# Tracer-1_3.net
KiCad netlist of a schematic drawn in EasyEDA Pro
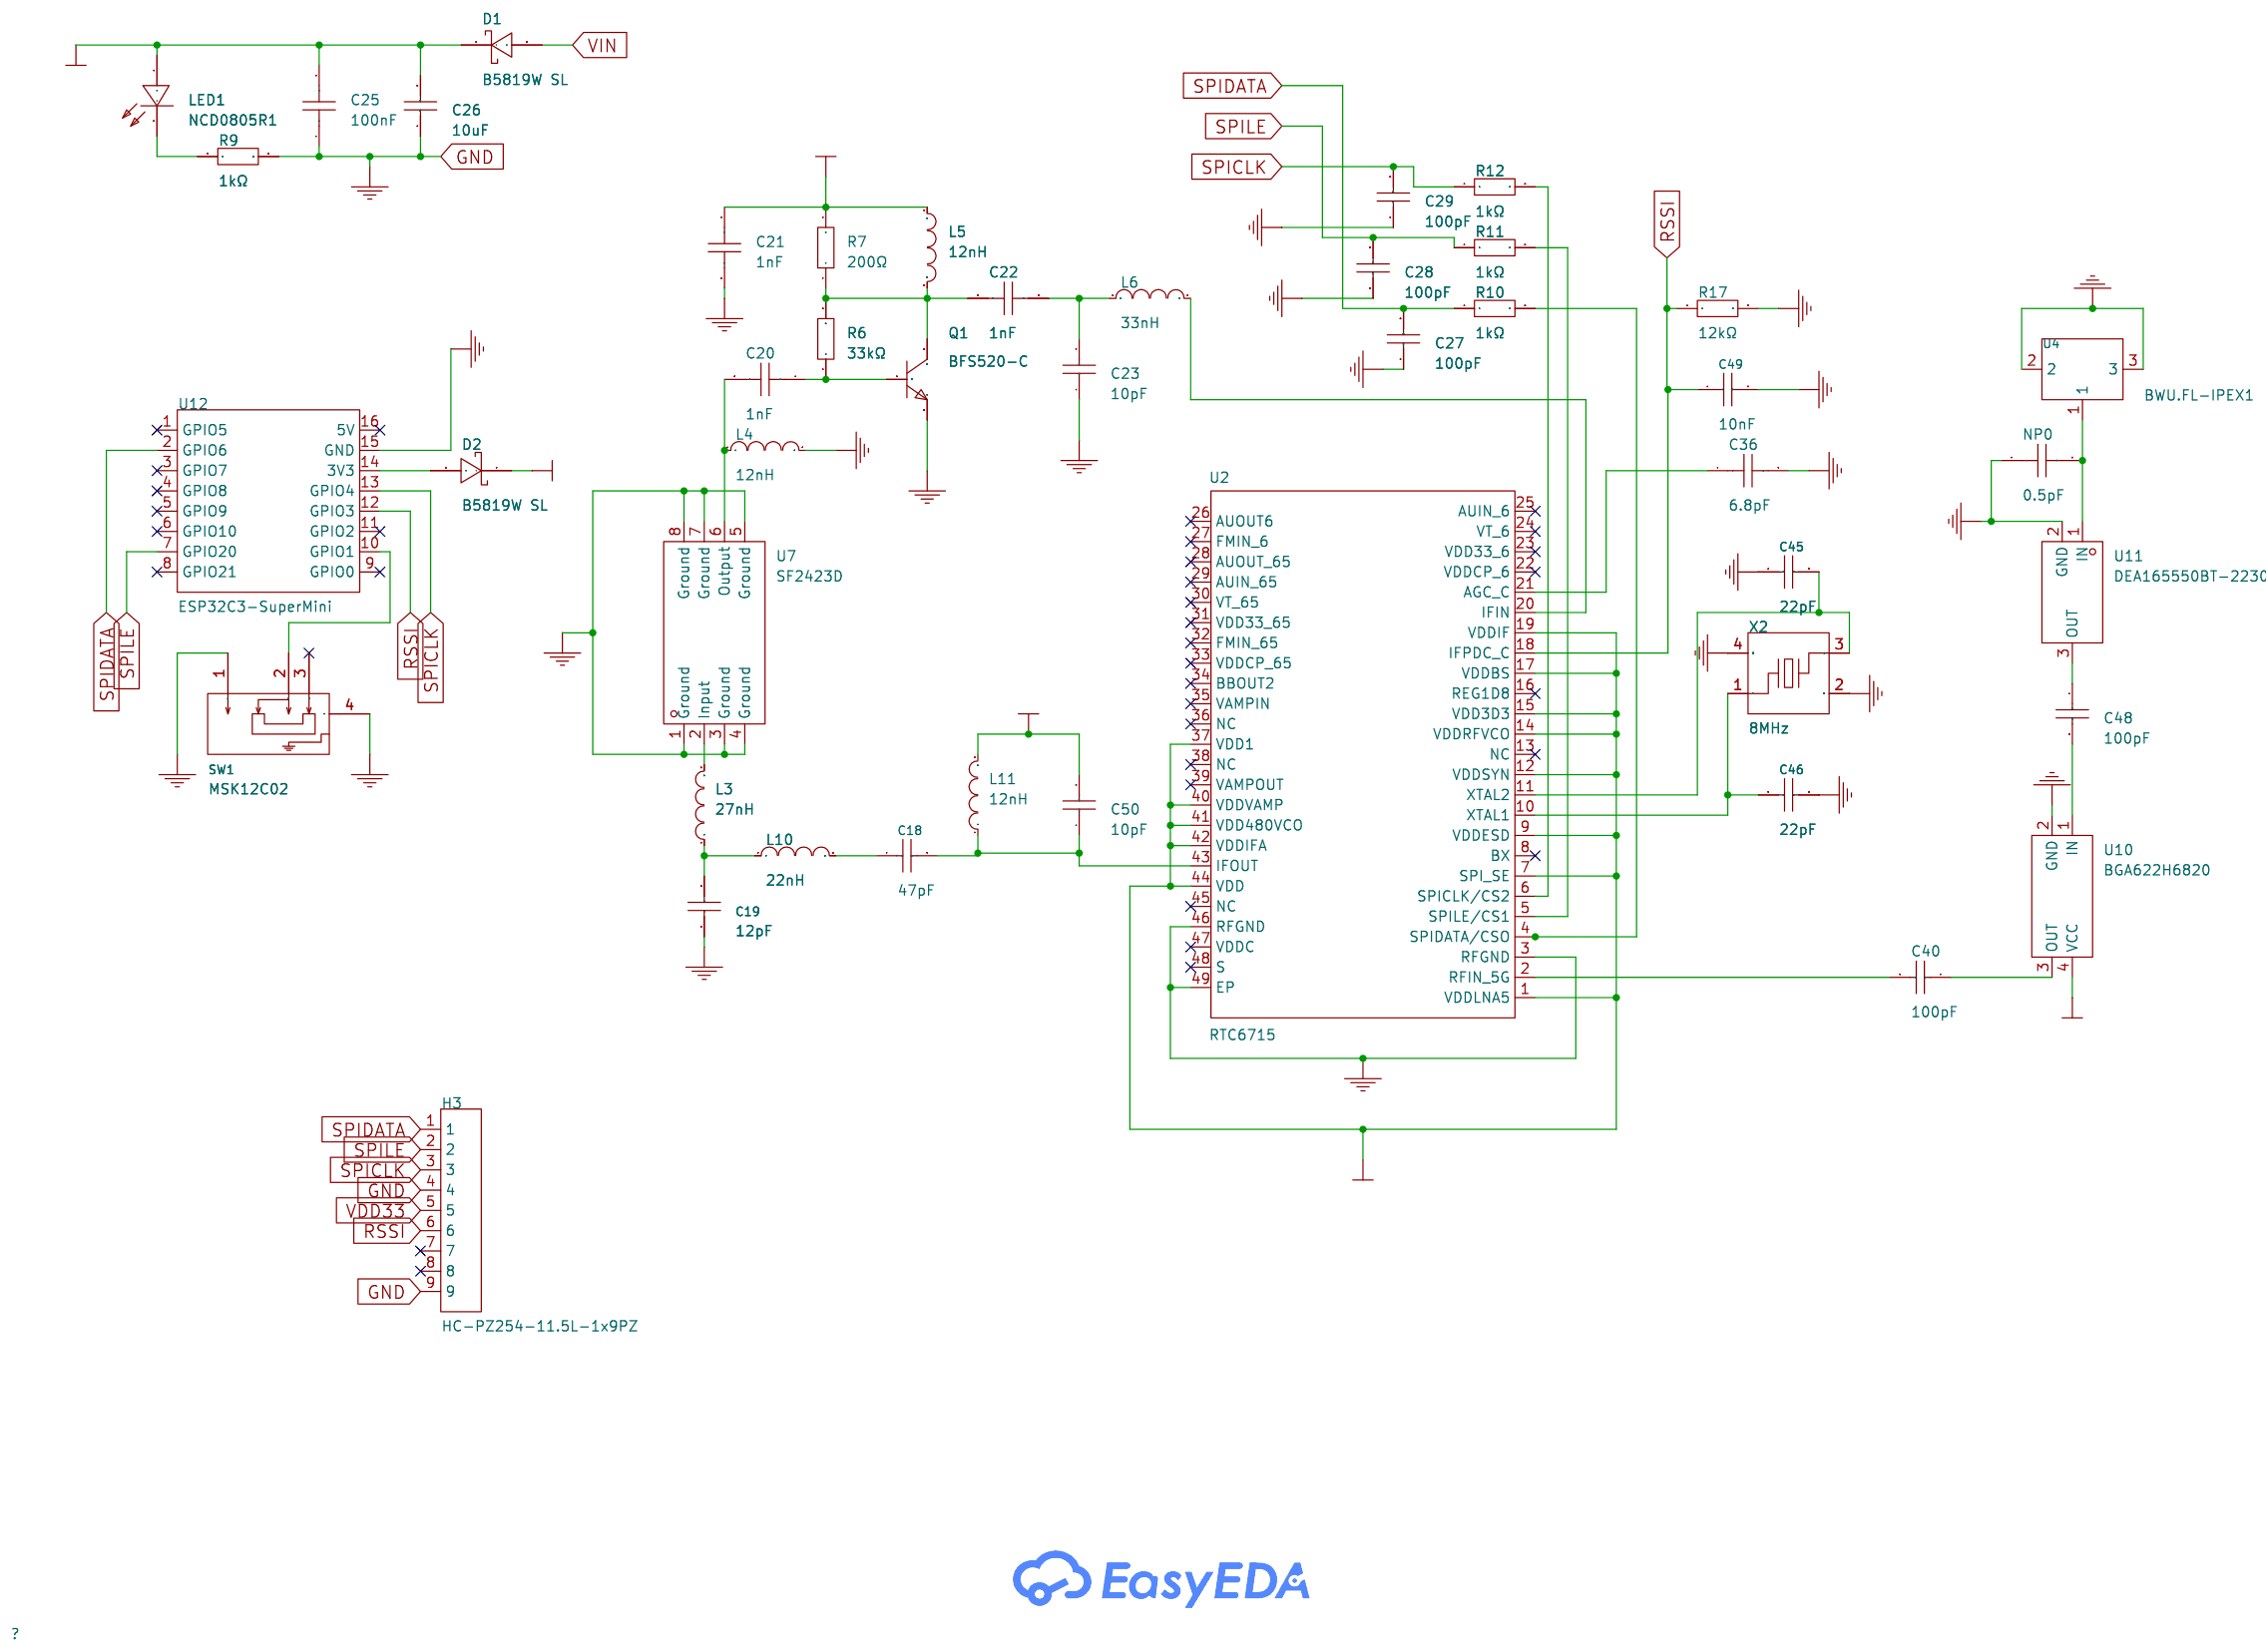
[diagram p0: schematic sheet]

(export (version "E")
  (design (tool "Eeschema 10.0.6"))
  (components
    (comp (ref "C18")
      (value "47pF")
      (footprint "easyedapro:C0402")
      (fields
        (field (name "Manufacturer Part") "CC0402JRNPO9BN470")
        (field (name "Manufacturer") "YAGEO(国巨)")
      )
      (libsource (lib "easyedapro") (part "CC0402JRNPO9BN470"))
    )
    (comp (ref "C19")
      (value "12pF")
      (footprint "easyedapro:C0402")
      (fields
        (field (name "Manufacturer Part") "GRM1555C1H120JA01D")
        (field (name "Manufacturer") "muRata(村田)")
      )
      (libsource (lib "easyedapro") (part "GRM1555C1H120JA01D"))
    )
    (comp (ref "C20")
      (value "1nF")
      (footprint "easyedapro:C0402")
      (fields
        (field (name "Manufacturer Part") "GRM155R71H102KA01D")
        (field (name "Manufacturer") "muRata(村田)")
      )
      (libsource (lib "easyedapro") (part "GRM155R71H102KA01D"))
    )
    (comp (ref "C21")
      (value "1nF")
      (footprint "easyedapro:C0402")
      (fields
        (field (name "Manufacturer Part") "GRM155R71H102KA01D")
        (field (name "Manufacturer") "muRata(村田)")
      )
      (libsource (lib "easyedapro") (part "GRM155R71H102KA01D"))
    )
    (comp (ref "C22")
      (value "1nF")
      (footprint "easyedapro:C0402")
      (fields
        (field (name "Manufacturer Part") "GRM155R71H102KA01D")
        (field (name "Manufacturer") "muRata(村田)")
      )
      (libsource (lib "easyedapro") (part "GRM155R71H102KA01D"))
    )
    (comp (ref "C23")
      (value "10pF")
      (footprint "easyedapro:C0402")
      (fields
        (field (name "Manufacturer Part") "GRM1555C1H100JA01D")
        (field (name "Manufacturer") "muRata(村田)")
      )
      (libsource (lib "easyedapro") (part "GRM1555C1H100JA01D"))
    )
    (comp (ref "C25")
      (value "100nF")
      (footprint "easyedapro:C0402")
      (fields
        (field (name "Manufacturer Part") "CL05B104KO5NNNC")
        (field (name "Manufacturer") "SAMSUNG(三星)")
      )
      (libsource (lib "easyedapro") (part "CL05B104KO5NNNC"))
    )
    (comp (ref "C26")
      (value "10uF")
      (fields
        (field (name "Manufacturer Part") "GRM155R60J106ME44D")
        (field (name "Manufacturer") "muRata(村田)")
      )
      (libsource (lib "easyedapro") (part "CL05A106MQ5NUNC"))
    )
    (comp (ref "C27")
      (value "100pF")
      (footprint "easyedapro:C0402")
      (fields
        (field (name "Manufacturer Part") "GRM1555C1H101JA01D")
        (field (name "Manufacturer") "muRata(村田)")
      )
      (libsource (lib "easyedapro") (part "GRM1555C1H101JA01D"))
    )
    (comp (ref "C28")
      (value "100pF")
      (footprint "easyedapro:C0402")
      (fields
        (field (name "Manufacturer Part") "GRM1555C1H101JA01D")
        (field (name "Manufacturer") "muRata(村田)")
      )
      (libsource (lib "easyedapro") (part "GRM1555C1H101JA01D"))
    )
    (comp (ref "C29")
      (value "100pF")
      (footprint "easyedapro:C0402")
      (fields
        (field (name "Manufacturer Part") "GRM1555C1H101JA01D")
        (field (name "Manufacturer") "muRata(村田)")
      )
      (libsource (lib "easyedapro") (part "GRM1555C1H101JA01D"))
    )
    (comp (ref "C36")
      (value "6.8pF")
      (footprint "easyedapro:C0402")
      (fields
        (field (name "Manufacturer Part") "CC0402CRNPO9BN6R8")
        (field (name "Manufacturer") "YAGEO(国巨)")
      )
      (libsource (lib "easyedapro") (part "CC0402CRNPO9BN6R8"))
    )
    (comp (ref "C40")
      (value "100pF")
      (footprint "easyedapro:C0402")
      (fields
        (field (name "Manufacturer Part") "GRM1555C1H101JA01D")
        (field (name "Manufacturer") "muRata(村田)")
      )
      (libsource (lib "easyedapro") (part "GRM1555C1H101JA01D"))
    )
    (comp (ref "C45")
      (value "22pF")
      (footprint "easyedapro:C0402")
      (fields
        (field (name "Manufacturer Part") "CC0402JRNPO9BN220")
        (field (name "Manufacturer") "YAGEO(国巨)")
      )
      (libsource (lib "easyedapro") (part "CC0402JRNPO9BN220"))
    )
    (comp (ref "C46")
      (value "22pF")
      (footprint "easyedapro:C0402")
      (fields
        (field (name "Manufacturer Part") "CC0402JRNPO9BN220")
        (field (name "Manufacturer") "YAGEO(国巨)")
      )
      (libsource (lib "easyedapro") (part "CC0402JRNPO9BN220"))
    )
    (comp (ref "C48")
      (value "100pF")
      (footprint "easyedapro:C0402")
      (fields
        (field (name "Manufacturer Part") "GRM1555C1H101JA01D")
        (field (name "Manufacturer") "muRata(村田)")
      )
      (libsource (lib "easyedapro") (part "GRM1555C1H101JA01D"))
    )
    (comp (ref "C49")
      (value "10nF")
      (footprint "easyedapro:C0402")
      (description "Capacitance:10nF Tolerance:±10% Tolerance:±10% Voltage Rating:50V Temperature Coefficient:X7R")
      (fields
        (field (name "Manufacturer Part") "CC0402KRX7R9BB103")
        (field (name "Manufacturer") "YAGEO(国巨)")
      )
      (libsource (lib "easyedapro") (part "CC0402KRX7R9BB103"))
    )
    (comp (ref "C50")
      (value "10pF")
      (footprint "easyedapro:C0402")
      (fields
        (field (name "Manufacturer Part") "GRM1555C1H100JA01D")
        (field (name "Manufacturer") "muRata(村田)")
      )
      (libsource (lib "easyedapro") (part "GRM1555C1H100JA01D"))
    )
    (comp (ref "D1")
      (value "B5819W SL")
      (footprint "easyedapro:SOD-123_L2.7-W1.6-LS3.7-RD-1")
      (description "Forward Voltage (Vf@If):600mV@1A Reverse Voltage (Vr):40V Rectified Current:1A")
      (fields (field (name "Manufacturer") "CJ(江苏长电/长晶)"))
      (libsource (lib "easyedapro") (part "B5819W_C8598"))
    )
    (comp (ref "D2")
      (value "B5819W SL")
      (footprint "easyedapro:SOD-123_L2.7-W1.6-LS3.7-RD-1")
      (description "Forward Voltage (Vf@If):600mV@1A Reverse Voltage (Vr):40V Rectified Current:1A")
      (fields (field (name "Manufacturer") "CJ(江苏长电/长晶)"))
      (libsource (lib "easyedapro") (part "B5819W_C8598"))
    )
    (comp (ref "H3")
      (value "HC-PZ254-11.5L-1x9PZ")
      (footprint "easyedapro:HDR-TH_9P-P2.54-V-M")
      (fields (field (name "Manufacturer") "HC(虹成电子)"))
      (libsource (lib "easyedapro") (part "HC-PZ254-11.5L-1X9PZ"))
    )
    (comp (ref "L3")
      (value "27nH")
      (footprint "easyedapro:L0402-RD")
      (fields (field (name "Manufacturer Part") "LQG15HS27NJ02D") (field (name "Manufacturer") "muRata(村田)"))
      (libsource (lib "easyedapro") (part "LQG15HS27NJ02D"))
    )
    (comp (ref "L4")
      (value "12nH")
      (footprint "easyedapro:L0402")
      (fields (field (name "Manufacturer Part") "LQW15AN12NG00D") (field (name "Manufacturer") "muRata(村田)"))
      (libsource (lib "easyedapro") (part "LQW15AN12NG00D"))
    )
    (comp (ref "L5")
      (value "12nH")
      (footprint "easyedapro:L0402")
      (fields (field (name "Manufacturer Part") "LQW15AN12NG00D") (field (name "Manufacturer") "muRata(村田)"))
      (libsource (lib "easyedapro") (part "LQW15AN12NG00D"))
    )
    (comp (ref "L6")
      (value "33nH")
      (footprint "easyedapro:L0402")
      (fields (field (name "Manufacturer Part") "LQG15HS33NJ02D") (field (name "Manufacturer") "muRata(村田)"))
      (libsource (lib "easyedapro") (part "LQG15HS33NJ02D"))
    )
    (comp (ref "L10")
      (value "22nH")
      (footprint "easyedapro:L0402")
      (fields (field (name "Manufacturer Part") "LQW15AN22NJ00D") (field (name "Manufacturer") "muRata(村田)"))
      (libsource (lib "easyedapro") (part "LQW15AN22NJ00D"))
    )
    (comp (ref "L11")
      (value "12nH")
      (footprint "easyedapro:L0402")
      (fields (field (name "Manufacturer Part") "LQW15AN12NG00D") (field (name "Manufacturer") "muRata(村田)"))
      (libsource (lib "easyedapro") (part "LQW15AN12NG00D"))
    )
    (comp (ref "LED1")
      (value "NCD0805R1")
      (footprint "easyedapro:LED0805-R-RD")
      (fields (field (name "Manufacturer") "国星光电"))
      (libsource (lib "easyedapro") (part "FC-2012HRK-620D"))
    )
    (comp (ref "NP0")
      (value "0.5pF")
      (footprint "easyedapro:C0402")
      (description "Capacitance:0.5pF Voltage Rating:50V Temperature Coefficient:C0G")
      (fields (field (name "Manufacturer Part") "0402CG0R5B500NT") (field (name "Manufacturer") "FH(风华)"))
      (libsource (lib "easyedapro") (part "0402CG0R5B500NT"))
    )
    (comp (ref "Q1")
      (value "BFS520-C")
      (footprint "easyedapro:SOT-323-3_L2.0-W1.3-P1.30-LS2.3-BR")
      (fields (field (name "Manufacturer") "Slkor(萨科微)"))
      (libsource (lib "easyedapro") (part "BFS520-C"))
    )
    (comp (ref "R6")
      (value "33kΩ")
      (footprint "easyedapro:R0402")
      (fields (field (name "Manufacturer Part") "RC0402FR-0733KL") (field (name "Manufacturer") "YAGEO(国巨)"))
      (libsource (lib "easyedapro") (part "RC0402FR-0733KL"))
    )
    (comp (ref "R7")
      (value "200Ω")
      (footprint "easyedapro:R0402")
      (fields (field (name "Manufacturer Part") "RC0402FR-07200RL") (field (name "Manufacturer") "YAGEO(国巨)"))
      (libsource (lib "easyedapro") (part "RC0402FR-07200RL"))
    )
    (comp (ref "R9")
      (value "1kΩ")
      (footprint "easyedapro:R0402")
      (fields (field (name "Manufacturer Part") "RC0402FR-071KL") (field (name "Manufacturer") "YAGEO(国巨)"))
      (libsource (lib "easyedapro") (part "RC0402FR-071KL"))
    )
    (comp (ref "R10")
      (value "1kΩ")
      (footprint "easyedapro:R0402")
      (fields (field (name "Manufacturer Part") "RC0402FR-071KL") (field (name "Manufacturer") "YAGEO(国巨)"))
      (libsource (lib "easyedapro") (part "RC0402FR-071KL"))
    )
    (comp (ref "R11")
      (value "1kΩ")
      (footprint "easyedapro:R0402")
      (fields (field (name "Manufacturer Part") "RC0402FR-071KL") (field (name "Manufacturer") "YAGEO(国巨)"))
      (libsource (lib "easyedapro") (part "RC0402FR-071KL"))
    )
    (comp (ref "R12")
      (value "1kΩ")
      (footprint "easyedapro:R0402")
      (fields (field (name "Manufacturer Part") "RC0402FR-071KL") (field (name "Manufacturer") "YAGEO(国巨)"))
      (libsource (lib "easyedapro") (part "RC0402FR-071KL"))
    )
    (comp (ref "R17")
      (value "12kΩ")
      (footprint "easyedapro:R0402")
      (fields (field (name "Manufacturer Part") "RTT021202FTH") (field (name "Manufacturer") "RALEC(旺诠)"))
      (libsource (lib "easyedapro") (part "RTT021202FTH"))
    )
    (comp (ref "SW1")
      (value "MSK12C02")
      (footprint "easyedapro:SW-TH_MSK12C02")
      (fields (field (name "Manufacturer") "SHOU HAN(首韩)"))
      (libsource (lib "easyedapro") (part "MSK12C02"))
    )
    (comp (ref "U2") (value "RTC6715") (libsource (lib "easyedapro") (part "RTC6715")))
    (comp (ref "U4")
      (value "BWU.FL-IPEX1")
      (footprint "easyedapro:IPEX-SMD_BWIPX-1-001E")
      (fields (field (name "Manufacturer") "BAT WIRELESS(蝙蝠无线)"))
      (libsource (lib "easyedapro") (part "BWU.FL-IPEX1"))
    )
    (comp (ref "U7")
      (value "SF2423D")
      (footprint "easyedapro:FILTER-SMD_8P-L3.8-W3.8-P1.27-BL")
      (fields (field (name "Manufacturer") "muRata(村田)"))
      (libsource (lib "easyedapro") (part "SF2423D"))
    )
    (comp (ref "U10")
      (value "BGA622H6820")
      (footprint "easyedapro:SOT-343-4_L2.0-W1.3-P1.30-LS2.1-BL")
      (fields (field (name "Manufacturer") "Infineon(英飞凌)"))
      (libsource (lib "easyedapro") (part "BGA622H6820"))
    )
    (comp (ref "U11")
      (value "DEA165550BT-2230C2-H")
      (footprint "easyedapro:FILTER-SMD_3P-L1.6-W0.8-L-1")
      (description "Bandwidth:800MHz Filter Type:Bandpass Insertion Loss:0.9dB")
      (fields (field (name "Manufacturer") "TDK"))
      (libsource (lib "easyedapro") (part "DEA165550BT-2230C2-H"))
    )
    (comp (ref "U12")
      (value "ESP32C3-SuperMini")
      (footprint "easyedapro:COMM-SMD_16P-L22.5-W18.0-P2.54-TL")
      (libsource (lib "easyedapro") (part "ESP32C3-SUPERMINI"))
    )
    (comp (ref "X2")
      (value "8MHz")
      (footprint "easyedapro:CRYSTAL-SMD_4P-L3.2-W2.5-BL")
      (fields (field (name "Manufacturer Part") "K3A080001210") (field (name "Manufacturer") "KYX(凯越翔)"))
      (libsource (lib "easyedapro") (part "K3A080001210"))
    )
  )
  (nets
    (net (code "1") (name "GND") (class "Default")
      (node (ref "C19") (pin "1") (pinfunction "1_1") (pintype "input"))
      (node (ref "C21") (pin "2") (pinfunction "2_2") (pintype "unspecified"))
      (node (ref "C23") (pin "1") (pinfunction "1_1") (pintype "input"))
      (node (ref "C25") (pin "1") (pinfunction "1_1") (pintype "unspecified"))
      (node (ref "C26") (pin "1") (pinfunction "1_1") (pintype "input"))
      (node (ref "C27") (pin "1") (pinfunction "1_1") (pintype "input"))
      (node (ref "C28") (pin "1") (pinfunction "1_1") (pintype "input"))
      (node (ref "C29") (pin "1") (pinfunction "1_1") (pintype "input"))
      (node (ref "C36") (pin "2") (pinfunction "2_2") (pintype "unspecified"))
      (node (ref "C45") (pin "1") (pinfunction "1_1") (pintype "input"))
      (node (ref "C46") (pin "2") (pinfunction "2_2") (pintype "input"))
      (node (ref "C49") (pin "2") (pinfunction "2_2") (pintype "input"))
      (node (ref "H3") (pin "4") (pinfunction "4_4") (pintype "unspecified"))
      (node (ref "H3") (pin "9") (pinfunction "9_9") (pintype "unspecified"))
      (node (ref "L4") (pin "2") (pinfunction "2_2") (pintype "unspecified"))
      (node (ref "NP0") (pin "1") (pinfunction "1_1") (pintype "unspecified"))
      (node (ref "Q1") (pin "2") (pinfunction "E_2") (pintype "input"))
      (node (ref "R17") (pin "2") (pinfunction "2_2") (pintype "input"))
      (node (ref "R9") (pin "2") (pinfunction "2_2") (pintype "input"))
      (node (ref "SW1") (pin "1") (pinfunction "1_1") (pintype "input"))
      (node (ref "SW1") (pin "4") (pinfunction "4_4") (pintype "input"))
      (node (ref "U10") (pin "2") (pinfunction "GND_2") (pintype "unspecified"))
      (node (ref "U11") (pin "2") (pinfunction "GND_2") (pintype "unspecified"))
      (node (ref "U12") (pin "15") (pinfunction "GND_15") (pintype "unspecified"))
      (node (ref "U2") (pin "3") (pinfunction "RFGND_3") (pintype "unspecified"))
      (node (ref "U2") (pin "46") (pinfunction "RFGND_46") (pintype "unspecified"))
      (node (ref "U2") (pin "49") (pinfunction "EP_49") (pintype "unspecified"))
      (node (ref "U4") (pin "2") (pinfunction "2_2") (pintype "input"))
      (node (ref "U4") (pin "3") (pinfunction "3_3") (pintype "input"))
      (node (ref "U7") (pin "1") (pinfunction "Ground_1") (pintype "unspecified"))
      (node (ref "U7") (pin "3") (pinfunction "Ground_3") (pintype "unspecified"))
      (node (ref "U7") (pin "4") (pinfunction "Ground_4") (pintype "unspecified"))
      (node (ref "U7") (pin "5") (pinfunction "Ground_5") (pintype "unspecified"))
      (node (ref "U7") (pin "7") (pinfunction "Ground_7") (pintype "unspecified"))
      (node (ref "U7") (pin "8") (pinfunction "Ground_8") (pintype "unspecified"))
      (node (ref "X2") (pin "2") (pinfunction "GND_2") (pintype "input"))
      (node (ref "X2") (pin "4") (pinfunction "GND_4") (pintype "input"))
    )
    (net (code "2") (name "Net-(C18-Pad1)") (class "Default")
      (node (ref "C18") (pin "1") (pinfunction "1_1") (pintype "input"))
      (node (ref "L10") (pin "2") (pinfunction "2_2") (pintype "unspecified"))
    )
    (net (code "3") (name "Net-(C19-Pad2)") (class "Default")
      (node (ref "C19") (pin "2") (pinfunction "2_2") (pintype "input"))
      (node (ref "L10") (pin "1") (pinfunction "1_1") (pintype "unspecified"))
      (node (ref "L3") (pin "1") (pinfunction "1_1") (pintype "unspecified"))
    )
    (net (code "4") (name "Net-(C22-Pad1)") (class "Default")
      (node (ref "C22") (pin "1") (pinfunction "1_1") (pintype "unspecified"))
      (node (ref "C23") (pin "2") (pinfunction "2_2") (pintype "input"))
      (node (ref "L6") (pin "1") (pinfunction "1_1") (pintype "unspecified"))
    )
    (net (code "5") (name "Net-(D2-+)") (class "Default")
      (node (ref "D2") (pin "2") (pinfunction "+_2") (pintype "unspecified"))
      (node (ref "U12") (pin "14") (pinfunction "3V3_14") (pintype "unspecified"))
    )
    (net (code "6") (name "Net-(LED1--)") (class "Default")
      (node (ref "LED1") (pin "2") (pinfunction "-_2") (pintype "unspecified"))
      (node (ref "R9") (pin "1") (pinfunction "1_1") (pintype "input"))
    )
    (net (code "7") (name "Net-(Q1-B)") (class "Default")
      (node (ref "C20") (pin "1") (pinfunction "1_1") (pintype "unspecified"))
      (node (ref "Q1") (pin "1") (pinfunction "B_1") (pintype "input"))
      (node (ref "R6") (pin "1") (pinfunction "1_1") (pintype "input"))
    )
    (net (code "8") (name "Net-(Q1-C)") (class "Default")
      (node (ref "C22") (pin "2") (pinfunction "2_2") (pintype "unspecified"))
      (node (ref "L5") (pin "2") (pinfunction "2_2") (pintype "unspecified"))
      (node (ref "Q1") (pin "3") (pinfunction "C_3") (pintype "input"))
      (node (ref "R6") (pin "2") (pinfunction "2_2") (pintype "input"))
      (node (ref "R7") (pin "1") (pinfunction "1_1") (pintype "input"))
    )
    (net (code "9") (name "Net-(U2-AGC_C)") (class "Default")
      (node (ref "C36") (pin "1") (pinfunction "1_1") (pintype "unspecified"))
      (node (ref "U2") (pin "21") (pinfunction "AGC_C_21") (pintype "unspecified"))
    )
    (net (code "10") (name "Net-(U2-IFIN)") (class "Default")
      (node (ref "L6") (pin "2") (pinfunction "2_2") (pintype "unspecified"))
      (node (ref "U2") (pin "20") (pinfunction "IFIN_20") (pintype "unspecified"))
    )
    (net (code "11") (name "Net-(U2-IFOUT)") (class "Default")
      (node (ref "C18") (pin "2") (pinfunction "2_2") (pintype "input"))
      (node (ref "C50") (pin "1") (pinfunction "1_1") (pintype "input"))
      (node (ref "L11") (pin "1") (pinfunction "1_1") (pintype "unspecified"))
      (node (ref "U2") (pin "43") (pinfunction "IFOUT_43") (pintype "unspecified"))
    )
    (net (code "12") (name "Net-(U2-RFIN_5G)") (class "Default")
      (node (ref "C40") (pin "2") (pinfunction "2_2") (pintype "input"))
      (node (ref "U2") (pin "2") (pinfunction "RFIN_5G_2") (pintype "unspecified"))
    )
    (net (code "13") (name "Net-(U2-SPICLK{slash}CS2)") (class "Default")
      (node (ref "R12") (pin "2") (pinfunction "2_2") (pintype "input"))
      (node (ref "U2") (pin "6") (pinfunction "SPICLK/CS2_6") (pintype "unspecified"))
    )
    (net (code "14") (name "Net-(U2-SPIDATA{slash}CSO)") (class "Default")
      (node (ref "R10") (pin "2") (pinfunction "2_2") (pintype "input"))
      (node (ref "U2") (pin "4") (pinfunction "SPIDATA/CSO_4") (pintype "unspecified"))
    )
    (net (code "15") (name "Net-(U2-SPILE{slash}CS1)") (class "Default")
      (node (ref "R11") (pin "2") (pinfunction "2_2") (pintype "input"))
      (node (ref "U2") (pin "5") (pinfunction "SPILE/CS1_5") (pintype "unspecified"))
    )
    (net (code "16") (name "Net-(U2-XTAL1)") (class "Default")
      (node (ref "C46") (pin "1") (pinfunction "1_1") (pintype "input"))
      (node (ref "U2") (pin "10") (pinfunction "XTAL1_10") (pintype "unspecified"))
      (node (ref "X2") (pin "1") (pinfunction "1_1") (pintype "input"))
    )
    (net (code "17") (name "Net-(U2-XTAL2)") (class "Default")
      (node (ref "C45") (pin "2") (pinfunction "2_2") (pintype "input"))
      (node (ref "U2") (pin "11") (pinfunction "XTAL2_11") (pintype "unspecified"))
      (node (ref "X2") (pin "3") (pinfunction "3_3") (pintype "input"))
    )
    (net (code "18") (name "Net-(U7-Input)") (class "Default")
      (node (ref "L3") (pin "2") (pinfunction "2_2") (pintype "unspecified"))
      (node (ref "U7") (pin "2") (pinfunction "Input_2") (pintype "unspecified"))
    )
    (net (code "19") (name "Net-(U7-Output)") (class "Default")
      (node (ref "C20") (pin "2") (pinfunction "2_2") (pintype "unspecified"))
      (node (ref "L4") (pin "1") (pinfunction "1_1") (pintype "unspecified"))
      (node (ref "U7") (pin "6") (pinfunction "Output_6") (pintype "unspecified"))
    )
    (net (code "20") (name "Net-(U10-IN)") (class "Default")
      (node (ref "C48") (pin "2") (pinfunction "2_2") (pintype "input"))
      (node (ref "U10") (pin "1") (pinfunction "IN_1") (pintype "unspecified"))
    )
    (net (code "21") (name "Net-(U10-OUT)") (class "Default")
      (node (ref "C40") (pin "1") (pinfunction "1_1") (pintype "input"))
      (node (ref "U10") (pin "3") (pinfunction "OUT_3") (pintype "unspecified"))
    )
    (net (code "22") (name "Net-(U11-IN)") (class "Default")
      (node (ref "NP0") (pin "2") (pinfunction "2_2") (pintype "unspecified"))
      (node (ref "U11") (pin "1") (pinfunction "IN_1") (pintype "unspecified"))
      (node (ref "U4") (pin "1") (pinfunction "1_1") (pintype "input"))
    )
    (net (code "23") (name "Net-(U11-OUT)") (class "Default")
      (node (ref "C48") (pin "1") (pinfunction "1_1") (pintype "input"))
      (node (ref "U11") (pin "3") (pinfunction "OUT_3") (pintype "unspecified"))
    )
    (net (code "24") (name "Net-(U12-GPIO1)") (class "Default")
      (node (ref "SW1") (pin "2") (pinfunction "2_2") (pintype "input"))
      (node (ref "U12") (pin "10") (pinfunction "GPIO1_10") (pintype "unspecified"))
    )
    (net (code "25") (name "RSSI") (class "Default")
      (node (ref "C49") (pin "1") (pinfunction "1_1") (pintype "input"))
      (node (ref "H3") (pin "6") (pinfunction "6_6") (pintype "unspecified"))
      (node (ref "R17") (pin "1") (pinfunction "1_1") (pintype "input"))
      (node (ref "U12") (pin "12") (pinfunction "GPIO3_12") (pintype "unspecified"))
      (node (ref "U2") (pin "18") (pinfunction "IFPDC_C_18") (pintype "unspecified"))
    )
    (net (code "26") (name "SPICLK") (class "Default")
      (node (ref "C29") (pin "2") (pinfunction "2_2") (pintype "input"))
      (node (ref "H3") (pin "3") (pinfunction "3_3") (pintype "unspecified"))
      (node (ref "R12") (pin "1") (pinfunction "1_1") (pintype "input"))
      (node (ref "U12") (pin "13") (pinfunction "GPIO4_13") (pintype "unspecified"))
    )
    (net (code "27") (name "SPIDATA") (class "Default")
      (node (ref "C27") (pin "2") (pinfunction "2_2") (pintype "input"))
      (node (ref "H3") (pin "1") (pinfunction "1_1") (pintype "unspecified"))
      (node (ref "R10") (pin "1") (pinfunction "1_1") (pintype "input"))
      (node (ref "U12") (pin "2") (pinfunction "GPIO6_2") (pintype "unspecified"))
    )
    (net (code "28") (name "SPILE") (class "Default")
      (node (ref "C28") (pin "2") (pinfunction "2_2") (pintype "input"))
      (node (ref "H3") (pin "2") (pinfunction "2_2") (pintype "unspecified"))
      (node (ref "R11") (pin "1") (pinfunction "1_1") (pintype "input"))
      (node (ref "U12") (pin "7") (pinfunction "GPIO20_7") (pintype "unspecified"))
    )
    (net (code "29") (name "VDD33") (class "Default")
      (node (ref "C21") (pin "1") (pinfunction "1_1") (pintype "unspecified"))
      (node (ref "C25") (pin "2") (pinfunction "2_2") (pintype "unspecified"))
      (node (ref "C26") (pin "2") (pinfunction "2_2") (pintype "input"))
      (node (ref "C50") (pin "2") (pinfunction "2_2") (pintype "input"))
      (node (ref "D1") (pin "1") (pinfunction "-_1") (pintype "unspecified"))
      (node (ref "D2") (pin "1") (pinfunction "-_1") (pintype "unspecified"))
      (node (ref "H3") (pin "5") (pinfunction "5_5") (pintype "unspecified"))
      (node (ref "L11") (pin "2") (pinfunction "2_2") (pintype "unspecified"))
      (node (ref "L5") (pin "1") (pinfunction "1_1") (pintype "unspecified"))
      (node (ref "LED1") (pin "1") (pinfunction "+_1") (pintype "unspecified"))
      (node (ref "R7") (pin "2") (pinfunction "2_2") (pintype "input"))
      (node (ref "U10") (pin "4") (pinfunction "VCC_4") (pintype "unspecified"))
      (node (ref "U2") (pin "1") (pinfunction "VDDLNA5_1") (pintype "unspecified"))
      (node (ref "U2") (pin "12") (pinfunction "VDDSYN_12") (pintype "unspecified"))
      (node (ref "U2") (pin "14") (pinfunction "VDDRFVCO_14") (pintype "unspecified"))
      (node (ref "U2") (pin "15") (pinfunction "VDD3D3_15") (pintype "unspecified"))
      (node (ref "U2") (pin "17") (pinfunction "VDDBS_17") (pintype "unspecified"))
      (node (ref "U2") (pin "19") (pinfunction "VDDIF_19") (pintype "unspecified"))
      (node (ref "U2") (pin "37") (pinfunction "VDD1_37") (pintype "unspecified"))
      (node (ref "U2") (pin "40") (pinfunction "VDDVAMP_40") (pintype "unspecified"))
      (node (ref "U2") (pin "41") (pinfunction "VDD480VCO_41") (pintype "unspecified"))
      (node (ref "U2") (pin "42") (pinfunction "VDDIFA_42") (pintype "unspecified"))
      (node (ref "U2") (pin "44") (pinfunction "VDD_44") (pintype "unspecified"))
      (node (ref "U2") (pin "7") (pinfunction "SPI_SE_7") (pintype "unspecified"))
      (node (ref "U2") (pin "9") (pinfunction "VDDESD_9") (pintype "unspecified"))
    )
    (net (code "30") (name "VIN") (class "Default")
      (node (ref "D1") (pin "2") (pinfunction "+_2") (pintype "unspecified"))
    )
    (net (code "31") (name "unconnected-(H3-Pad7)") (class "Default")
      (node (ref "H3") (pin "7") (pinfunction "7_7") (pintype "unspecified+no_connect"))
    )
    (net (code "32") (name "unconnected-(H3-Pad8)") (class "Default")
      (node (ref "H3") (pin "8") (pinfunction "8_8") (pintype "unspecified+no_connect"))
    )
    (net (code "33") (name "unconnected-(SW1-Pad3)") (class "Default")
      (node (ref "SW1") (pin "3") (pinfunction "3_3") (pintype "input+no_connect"))
    )
    (net (code "34") (name "unconnected-(U2-AUIN_6-Pad25)") (class "Default")
      (node (ref "U2") (pin "25") (pinfunction "AUIN_6_25") (pintype "unspecified+no_connect"))
    )
    (net (code "35") (name "unconnected-(U2-AUIN_65-Pad29)") (class "Default")
      (node (ref "U2") (pin "29") (pinfunction "AUIN_65_29") (pintype "unspecified+no_connect"))
    )
    (net (code "36") (name "unconnected-(U2-AUOUT6-Pad26)") (class "Default")
      (node (ref "U2") (pin "26") (pinfunction "AUOUT6_26") (pintype "unspecified+no_connect"))
    )
    (net (code "37") (name "unconnected-(U2-AUOUT_65-Pad28)") (class "Default")
      (node (ref "U2") (pin "28") (pinfunction "AUOUT_65_28") (pintype "unspecified+no_connect"))
    )
    (net (code "38") (name "unconnected-(U2-BBOUT2-Pad34)") (class "Default")
      (node (ref "U2") (pin "34") (pinfunction "BBOUT2_34") (pintype "unspecified+no_connect"))
    )
    (net (code "39") (name "unconnected-(U2-BX-Pad8)") (class "Default")
      (node (ref "U2") (pin "8") (pinfunction "BX_8") (pintype "unspecified+no_connect"))
    )
    (net (code "40") (name "unconnected-(U2-FMIN_6-Pad27)") (class "Default")
      (node (ref "U2") (pin "27") (pinfunction "FMIN_6_27") (pintype "unspecified+no_connect"))
    )
    (net (code "41") (name "unconnected-(U2-FMIN_65-Pad32)") (class "Default")
      (node (ref "U2") (pin "32") (pinfunction "FMIN_65_32") (pintype "unspecified+no_connect"))
    )
    (net (code "42") (name "unconnected-(U2-NC-Pad13)") (class "Default")
      (node (ref "U2") (pin "13") (pinfunction "NC_13") (pintype "unspecified+no_connect"))
    )
    (net (code "43") (name "unconnected-(U2-NC-Pad36)") (class "Default")
      (node (ref "U2") (pin "36") (pinfunction "NC_36") (pintype "unspecified+no_connect"))
    )
    (net (code "44") (name "unconnected-(U2-NC-Pad38)") (class "Default")
      (node (ref "U2") (pin "38") (pinfunction "NC_38") (pintype "unspecified+no_connect"))
    )
    (net (code "45") (name "unconnected-(U2-NC-Pad45)") (class "Default")
      (node (ref "U2") (pin "45") (pinfunction "NC_45") (pintype "unspecified+no_connect"))
    )
    (net (code "46") (name "unconnected-(U2-REG1D8-Pad16)") (class "Default")
      (node (ref "U2") (pin "16") (pinfunction "REG1D8_16") (pintype "unspecified+no_connect"))
    )
    (net (code "47") (name "unconnected-(U2-S-Pad48)") (class "Default")
      (node (ref "U2") (pin "48") (pinfunction "S_48") (pintype "unspecified+no_connect"))
    )
    (net (code "48") (name "unconnected-(U2-VAMPIN-Pad35)") (class "Default")
      (node (ref "U2") (pin "35") (pinfunction "VAMPIN_35") (pintype "unspecified+no_connect"))
    )
    (net (code "49") (name "unconnected-(U2-VAMPOUT-Pad39)") (class "Default")
      (node (ref "U2") (pin "39") (pinfunction "VAMPOUT_39") (pintype "unspecified+no_connect"))
    )
    (net (code "50") (name "unconnected-(U2-VDD33_6-Pad23)") (class "Default")
      (node (ref "U2") (pin "23") (pinfunction "VDD33_6_23") (pintype "unspecified+no_connect"))
    )
    (net (code "51") (name "unconnected-(U2-VDD33_65-Pad31)") (class "Default")
      (node (ref "U2") (pin "31") (pinfunction "VDD33_65_31") (pintype "unspecified+no_connect"))
    )
    (net (code "52") (name "unconnected-(U2-VDDC-Pad47)") (class "Default")
      (node (ref "U2") (pin "47") (pinfunction "VDDC_47") (pintype "unspecified+no_connect"))
    )
    (net (code "53") (name "unconnected-(U2-VDDCP_6-Pad22)") (class "Default")
      (node (ref "U2") (pin "22") (pinfunction "VDDCP_6_22") (pintype "unspecified+no_connect"))
    )
    (net (code "54") (name "unconnected-(U2-VDDCP_65-Pad33)") (class "Default")
      (node (ref "U2") (pin "33") (pinfunction "VDDCP_65_33") (pintype "unspecified+no_connect"))
    )
    (net (code "55") (name "unconnected-(U2-VT_6-Pad24)") (class "Default")
      (node (ref "U2") (pin "24") (pinfunction "VT_6_24") (pintype "unspecified+no_connect"))
    )
    (net (code "56") (name "unconnected-(U2-VT_65-Pad30)") (class "Default")
      (node (ref "U2") (pin "30") (pinfunction "VT_65_30") (pintype "unspecified+no_connect"))
    )
    (net (code "57") (name "unconnected-(U12-5V-Pad16)") (class "Default")
      (node (ref "U12") (pin "16") (pinfunction "5V_16") (pintype "unspecified+no_connect"))
    )
    (net (code "58") (name "unconnected-(U12-GPIO0-Pad9)") (class "Default")
      (node (ref "U12") (pin "9") (pinfunction "GPIO0_9") (pintype "unspecified+no_connect"))
    )
    (net (code "59") (name "unconnected-(U12-GPIO2-Pad11)") (class "Default")
      (node (ref "U12") (pin "11") (pinfunction "GPIO2_11") (pintype "unspecified+no_connect"))
    )
    (net (code "60") (name "unconnected-(U12-GPIO5-Pad1)") (class "Default")
      (node (ref "U12") (pin "1") (pinfunction "GPIO5_1") (pintype "unspecified+no_connect"))
    )
    (net (code "61") (name "unconnected-(U12-GPIO7-Pad3)") (class "Default")
      (node (ref "U12") (pin "3") (pinfunction "GPIO7_3") (pintype "unspecified+no_connect"))
    )
    (net (code "62") (name "unconnected-(U12-GPIO8-Pad4)") (class "Default")
      (node (ref "U12") (pin "4") (pinfunction "GPIO8_4") (pintype "unspecified+no_connect"))
    )
    (net (code "63") (name "unconnected-(U12-GPIO9-Pad5)") (class "Default")
      (node (ref "U12") (pin "5") (pinfunction "GPIO9_5") (pintype "unspecified+no_connect"))
    )
    (net (code "64") (name "unconnected-(U12-GPIO10-Pad6)") (class "Default")
      (node (ref "U12") (pin "6") (pinfunction "GPIO10_6") (pintype "unspecified+no_connect"))
    )
    (net (code "65") (name "unconnected-(U12-GPIO21-Pad8)") (class "Default")
      (node (ref "U12") (pin "8") (pinfunction "GPIO21_8") (pintype "unspecified+no_connect"))
    )
  )
)
